# Connectors.net
KiCad netlist of a schematic drawn in Altium Designer
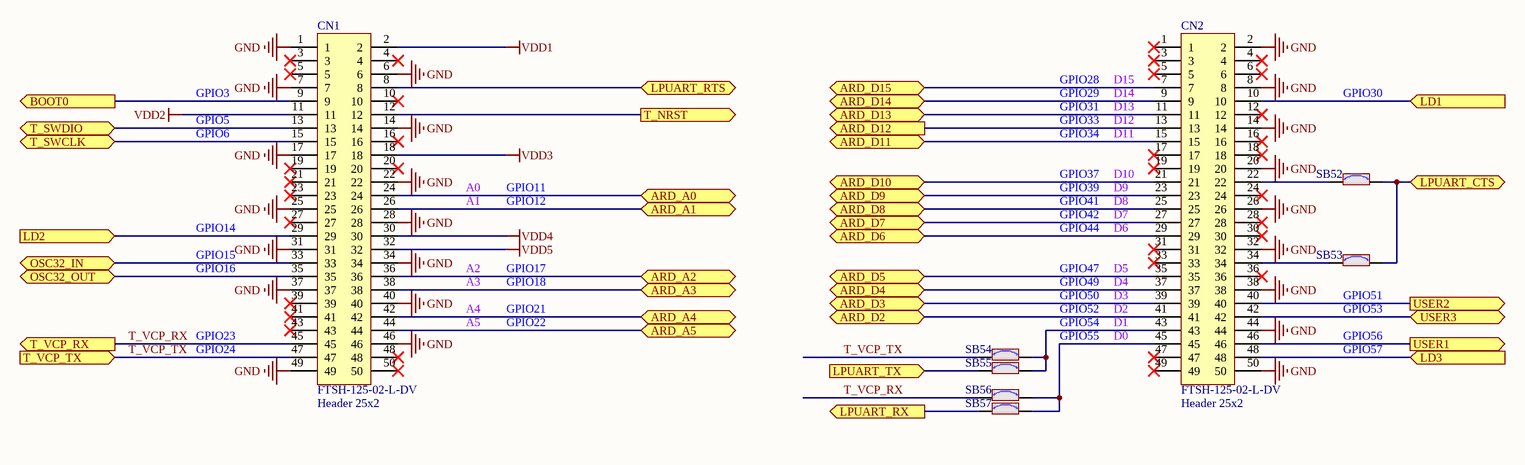
[diagram p0: Connectors.SchDoc]

(export (version "E")
  (design (tool "Eeschema 10.0.6"))
  (components
    (comp (ref "CN1")
      (value "FTSH-125-02-L-DV")
      (footprint "MCD_PARTS:CON_SAMTEC_FTSH-125-02-L-DV")
      (description "Header, 25x2, 12.7mm, VR, SMD, T=4.83mm")
      (fields
        (field (name "INTERNAL_PART_NUMBER") "MCD-02746")
        (field (name "ALTIUM_VALUE") "Header 25x2")
        (field (name "MANUFACTURER") "SAMTEC")
      )
      (libsource (lib "MCD_PARTS_database") (part "FTSH-125-02-L-DV"))
    )
    (comp (ref "CN2")
      (value "FTSH-125-02-L-DV")
      (footprint "MCD_PARTS:CON_SAMTEC_FTSH-125-02-L-DV")
      (description "Header, 25x2, 12.7mm, VR, SMD, T=4.83mm")
      (fields
        (field (name "INTERNAL_PART_NUMBER") "MCD-02746")
        (field (name "ALTIUM_VALUE") "Header 25x2")
        (field (name "MANUFACTURER") "SAMTEC")
      )
      (libsource (lib "MCD_PARTS_database") (part "FTSH-125-02-L-DV"))
    )
    (comp (ref "SB52")
      (value "SB_ON")
      (footprint "MCD_PARTS:SOLDER-BRIDGE_R0402-0R")
      (description "Solder Bridge 0402 ON")
      (fields (field (name "INTERNAL_PART_NUMBER") "MCD-01618") (field (name "MANUFACTURER") "YAGEO"))
      (libsource (lib "MCD_PARTS_database") (part "SB_ON"))
    )
    (comp (ref "SB53")
      (value "SB_ON")
      (footprint "MCD_PARTS:SOLDER-BRIDGE_R0402-0R")
      (description "Solder Bridge 0402 ON")
      (fields (field (name "INTERNAL_PART_NUMBER") "MCD-01618") (field (name "MANUFACTURER") "YAGEO"))
      (libsource (lib "MCD_PARTS_database") (part "SB_ON"))
    )
    (comp (ref "SB54")
      (value "SB_ON")
      (footprint "MCD_PARTS:SOLDER-BRIDGE_R0402-0R")
      (description "Solder Bridge 0402 ON")
      (fields (field (name "INTERNAL_PART_NUMBER") "MCD-01618") (field (name "MANUFACTURER") "YAGEO"))
      (libsource (lib "MCD_PARTS_database") (part "SB_ON"))
    )
    (comp (ref "SB55")
      (value "SB_ON")
      (footprint "MCD_PARTS:SOLDER-BRIDGE_R0402-0R")
      (description "Solder Bridge 0402 ON")
      (fields (field (name "INTERNAL_PART_NUMBER") "MCD-01618") (field (name "MANUFACTURER") "YAGEO"))
      (libsource (lib "MCD_PARTS_database") (part "SB_ON"))
    )
    (comp (ref "SB56")
      (value "SB_ON")
      (footprint "MCD_PARTS:SOLDER-BRIDGE_R0402-0R")
      (description "Solder Bridge 0402 ON")
      (fields (field (name "INTERNAL_PART_NUMBER") "MCD-01618") (field (name "MANUFACTURER") "YAGEO"))
      (libsource (lib "MCD_PARTS_database") (part "SB_ON"))
    )
    (comp (ref "SB57")
      (value "SB_ON")
      (footprint "MCD_PARTS:SOLDER-BRIDGE_R0402-0R")
      (description "Solder Bridge 0402 ON")
      (fields (field (name "INTERNAL_PART_NUMBER") "MCD-01618") (field (name "MANUFACTURER") "YAGEO"))
      (libsource (lib "MCD_PARTS_database") (part "SB_ON"))
    )
  )
  (nets
    (net (code "1") (name "/ARD_A0") (class "Default")
      (node (ref "CN1") (pin "24") (pinfunction "24_24") (pintype "passive"))
    )
    (net (code "2") (name "/ARD_A1") (class "Default")
      (node (ref "CN1") (pin "26") (pinfunction "26_26") (pintype "passive"))
    )
    (net (code "3") (name "/ARD_A2") (class "Default")
      (node (ref "CN1") (pin "36") (pinfunction "36_36") (pintype "passive"))
    )
    (net (code "4") (name "/ARD_A3") (class "Default")
      (node (ref "CN1") (pin "38") (pinfunction "38_38") (pintype "passive"))
    )
    (net (code "5") (name "/ARD_A4") (class "Default")
      (node (ref "CN1") (pin "42") (pinfunction "42_42") (pintype "passive"))
    )
    (net (code "6") (name "/ARD_A5") (class "Default")
      (node (ref "CN1") (pin "44") (pinfunction "44_44") (pintype "passive"))
    )
    (net (code "7") (name "/ARD_D2") (class "Default")
      (node (ref "CN2") (pin "41") (pinfunction "41_41") (pintype "passive"))
    )
    (net (code "8") (name "/ARD_D3") (class "Default")
      (node (ref "CN2") (pin "39") (pinfunction "39_39") (pintype "passive"))
    )
    (net (code "9") (name "/ARD_D4") (class "Default")
      (node (ref "CN2") (pin "37") (pinfunction "37_37") (pintype "passive"))
    )
    (net (code "10") (name "/ARD_D5") (class "Default")
      (node (ref "CN2") (pin "35") (pinfunction "35_35") (pintype "passive"))
    )
    (net (code "11") (name "/ARD_D6") (class "Default")
      (node (ref "CN2") (pin "29") (pinfunction "29_29") (pintype "passive"))
    )
    (net (code "12") (name "/ARD_D7") (class "Default")
      (node (ref "CN2") (pin "27") (pinfunction "27_27") (pintype "passive"))
    )
    (net (code "13") (name "/ARD_D8") (class "Default")
      (node (ref "CN2") (pin "25") (pinfunction "25_25") (pintype "passive"))
    )
    (net (code "14") (name "/ARD_D9") (class "Default")
      (node (ref "CN2") (pin "23") (pinfunction "23_23") (pintype "passive"))
    )
    (net (code "15") (name "/ARD_D10") (class "Default")
      (node (ref "CN2") (pin "21") (pinfunction "21_21") (pintype "passive"))
    )
    (net (code "16") (name "/ARD_D11") (class "Default")
      (node (ref "CN2") (pin "15") (pinfunction "15_15") (pintype "passive"))
    )
    (net (code "17") (name "/ARD_D12") (class "Default")
      (node (ref "CN2") (pin "13") (pinfunction "13_13") (pintype "passive"))
    )
    (net (code "18") (name "/ARD_D13") (class "Default")
      (node (ref "CN2") (pin "11") (pinfunction "11_11") (pintype "passive"))
    )
    (net (code "19") (name "/ARD_D14") (class "Default")
      (node (ref "CN2") (pin "9") (pinfunction "9_9") (pintype "passive"))
    )
    (net (code "20") (name "/ARD_D15") (class "Default")
      (node (ref "CN2") (pin "7") (pinfunction "7_7") (pintype "passive"))
    )
    (net (code "21") (name "/BOOT0") (class "Default")
      (node (ref "CN1") (pin "9") (pinfunction "9_9") (pintype "passive"))
    )
    (net (code "22") (name "/LD1") (class "Default")
      (node (ref "CN2") (pin "10") (pinfunction "10_10") (pintype "passive"))
    )
    (net (code "23") (name "/LD2") (class "Default")
      (node (ref "CN1") (pin "29") (pinfunction "29_29") (pintype "passive"))
    )
    (net (code "24") (name "/LD3") (class "Default")
      (node (ref "CN2") (pin "48") (pinfunction "48_48") (pintype "passive"))
    )
    (net (code "25") (name "/LPUART_CTS") (class "Default")
      (node (ref "SB52") (pin "2") (pinfunction "2_2") (pintype "passive"))
      (node (ref "SB53") (pin "2") (pinfunction "2_2") (pintype "passive"))
    )
    (net (code "26") (name "/LPUART_RTS") (class "Default")
      (node (ref "CN1") (pin "8") (pinfunction "8_8") (pintype "passive"))
    )
    (net (code "27") (name "/LPUART_RX") (class "Default")
      (node (ref "SB57") (pin "1") (pinfunction "1_1") (pintype "passive"))
    )
    (net (code "28") (name "/LPUART_TX") (class "Default")
      (node (ref "SB55") (pin "1") (pinfunction "1_1") (pintype "passive"))
    )
    (net (code "29") (name "/OSC32_IN") (class "Default")
      (node (ref "CN1") (pin "33") (pinfunction "33_33") (pintype "passive"))
    )
    (net (code "30") (name "/OSC32_OUT") (class "Default")
      (node (ref "CN1") (pin "35") (pinfunction "35_35") (pintype "passive"))
    )
    (net (code "31") (name "/T_NRST") (class "Default")
      (node (ref "CN1") (pin "12") (pinfunction "12_12") (pintype "passive"))
    )
    (net (code "32") (name "/T_SWCLK") (class "Default")
      (node (ref "CN1") (pin "15") (pinfunction "15_15") (pintype "passive"))
    )
    (net (code "33") (name "/T_SWDIO") (class "Default")
      (node (ref "CN1") (pin "13") (pinfunction "13_13") (pintype "passive"))
    )
    (net (code "34") (name "/T_VCP_RX") (class "Default")
      (node (ref "CN1") (pin "45") (pinfunction "45_45") (pintype "passive"))
      (node (ref "SB56") (pin "1") (pinfunction "1_1") (pintype "passive"))
    )
    (net (code "35") (name "/T_VCP_TX") (class "Default")
      (node (ref "CN1") (pin "47") (pinfunction "47_47") (pintype "passive"))
      (node (ref "SB54") (pin "1") (pinfunction "1_1") (pintype "passive"))
    )
    (net (code "36") (name "/USER1") (class "Default")
      (node (ref "CN2") (pin "46") (pinfunction "46_46") (pintype "passive"))
    )
    (net (code "37") (name "/USER2") (class "Default")
      (node (ref "CN2") (pin "40") (pinfunction "40_40") (pintype "passive"))
    )
    (net (code "38") (name "/USER3") (class "Default")
      (node (ref "CN2") (pin "42") (pinfunction "42_42") (pintype "passive"))
    )
    (net (code "39") (name "GND") (class "Default")
      (node (ref "CN1") (pin "1") (pinfunction "1_1") (pintype "passive"))
      (node (ref "CN1") (pin "14") (pinfunction "14_14") (pintype "passive"))
      (node (ref "CN1") (pin "17") (pinfunction "17_17") (pintype "passive"))
      (node (ref "CN1") (pin "22") (pinfunction "22_22") (pintype "passive"))
      (node (ref "CN1") (pin "25") (pinfunction "25_25") (pintype "passive"))
      (node (ref "CN1") (pin "28") (pinfunction "28_28") (pintype "passive"))
      (node (ref "CN1") (pin "31") (pinfunction "31_31") (pintype "passive"))
      (node (ref "CN1") (pin "34") (pinfunction "34_34") (pintype "passive"))
      (node (ref "CN1") (pin "37") (pinfunction "37_37") (pintype "passive"))
      (node (ref "CN1") (pin "40") (pinfunction "40_40") (pintype "passive"))
      (node (ref "CN1") (pin "46") (pinfunction "46_46") (pintype "passive"))
      (node (ref "CN1") (pin "49") (pinfunction "49_49") (pintype "passive"))
      (node (ref "CN1") (pin "6") (pinfunction "6_6") (pintype "passive"))
      (node (ref "CN1") (pin "7") (pinfunction "7_7") (pintype "passive"))
      (node (ref "CN2") (pin "14") (pinfunction "14_14") (pintype "passive"))
      (node (ref "CN2") (pin "2") (pinfunction "2_2") (pintype "passive"))
      (node (ref "CN2") (pin "20") (pinfunction "20_20") (pintype "passive"))
      (node (ref "CN2") (pin "26") (pinfunction "26_26") (pintype "passive"))
      (node (ref "CN2") (pin "32") (pinfunction "32_32") (pintype "passive"))
      (node (ref "CN2") (pin "38") (pinfunction "38_38") (pintype "passive"))
      (node (ref "CN2") (pin "44") (pinfunction "44_44") (pintype "passive"))
      (node (ref "CN2") (pin "50") (pinfunction "50_50") (pintype "passive"))
      (node (ref "CN2") (pin "8") (pinfunction "8_8") (pintype "passive"))
    )
    (net (code "40") (name "Net-(CN2-Pad22)") (class "Default")
      (node (ref "CN2") (pin "22") (pinfunction "22_22") (pintype "passive"))
      (node (ref "SB52") (pin "1") (pinfunction "1_1") (pintype "passive"))
    )
    (net (code "41") (name "Net-(CN2-Pad34)") (class "Default")
      (node (ref "CN2") (pin "34") (pinfunction "34_34") (pintype "passive"))
      (node (ref "SB53") (pin "1") (pinfunction "1_1") (pintype "passive"))
    )
    (net (code "42") (name "Net-(CN2-Pad43)") (class "Default")
      (node (ref "CN2") (pin "43") (pinfunction "43_43") (pintype "passive"))
      (node (ref "SB54") (pin "2") (pinfunction "2_2") (pintype "passive"))
      (node (ref "SB55") (pin "2") (pinfunction "2_2") (pintype "passive"))
    )
    (net (code "43") (name "Net-(CN2-Pad45)") (class "Default")
      (node (ref "CN2") (pin "45") (pinfunction "45_45") (pintype "passive"))
      (node (ref "SB56") (pin "2") (pinfunction "2_2") (pintype "passive"))
      (node (ref "SB57") (pin "2") (pinfunction "2_2") (pintype "passive"))
    )
    (net (code "44") (name "VDD1") (class "Default")
      (node (ref "CN1") (pin "2") (pinfunction "2_2") (pintype "passive"))
    )
    (net (code "45") (name "VDD2") (class "Default")
      (node (ref "CN1") (pin "11") (pinfunction "11_11") (pintype "passive"))
    )
    (net (code "46") (name "VDD3") (class "Default")
      (node (ref "CN1") (pin "18") (pinfunction "18_18") (pintype "passive"))
    )
    (net (code "47") (name "VDD4") (class "Default")
      (node (ref "CN1") (pin "30") (pinfunction "30_30") (pintype "passive"))
    )
    (net (code "48") (name "VDD5") (class "Default")
      (node (ref "CN1") (pin "32") (pinfunction "32_32") (pintype "passive"))
    )
    (net (code "49") (name "unconnected-(CN1-Pad3)") (class "Default")
      (node (ref "CN1") (pin "3") (pinfunction "3_3") (pintype "passive+no_connect"))
    )
    (net (code "50") (name "unconnected-(CN1-Pad4)") (class "Default")
      (node (ref "CN1") (pin "4") (pinfunction "4_4") (pintype "passive+no_connect"))
    )
    (net (code "51") (name "unconnected-(CN1-Pad5)") (class "Default")
      (node (ref "CN1") (pin "5") (pinfunction "5_5") (pintype "passive+no_connect"))
    )
    (net (code "52") (name "unconnected-(CN1-Pad10)") (class "Default")
      (node (ref "CN1") (pin "10") (pinfunction "10_10") (pintype "passive+no_connect"))
    )
    (net (code "53") (name "unconnected-(CN1-Pad16)") (class "Default")
      (node (ref "CN1") (pin "16") (pinfunction "16_16") (pintype "passive+no_connect"))
    )
    (net (code "54") (name "unconnected-(CN1-Pad19)") (class "Default")
      (node (ref "CN1") (pin "19") (pinfunction "19_19") (pintype "passive+no_connect"))
    )
    (net (code "55") (name "unconnected-(CN1-Pad20)") (class "Default")
      (node (ref "CN1") (pin "20") (pinfunction "20_20") (pintype "passive+no_connect"))
    )
    (net (code "56") (name "unconnected-(CN1-Pad21)") (class "Default")
      (node (ref "CN1") (pin "21") (pinfunction "21_21") (pintype "passive+no_connect"))
    )
    (net (code "57") (name "unconnected-(CN1-Pad23)") (class "Default")
      (node (ref "CN1") (pin "23") (pinfunction "23_23") (pintype "passive+no_connect"))
    )
    (net (code "58") (name "unconnected-(CN1-Pad27)") (class "Default")
      (node (ref "CN1") (pin "27") (pinfunction "27_27") (pintype "passive+no_connect"))
    )
    (net (code "59") (name "unconnected-(CN1-Pad39)") (class "Default")
      (node (ref "CN1") (pin "39") (pinfunction "39_39") (pintype "passive+no_connect"))
    )
    (net (code "60") (name "unconnected-(CN1-Pad41)") (class "Default")
      (node (ref "CN1") (pin "41") (pinfunction "41_41") (pintype "passive+no_connect"))
    )
    (net (code "61") (name "unconnected-(CN1-Pad43)") (class "Default")
      (node (ref "CN1") (pin "43") (pinfunction "43_43") (pintype "passive+no_connect"))
    )
    (net (code "62") (name "unconnected-(CN1-Pad48)") (class "Default")
      (node (ref "CN1") (pin "48") (pinfunction "48_48") (pintype "passive+no_connect"))
    )
    (net (code "63") (name "unconnected-(CN1-Pad50)") (class "Default")
      (node (ref "CN1") (pin "50") (pinfunction "50_50") (pintype "passive+no_connect"))
    )
    (net (code "64") (name "unconnected-(CN2-Pad1)") (class "Default")
      (node (ref "CN2") (pin "1") (pinfunction "1_1") (pintype "passive+no_connect"))
    )
    (net (code "65") (name "unconnected-(CN2-Pad3)") (class "Default")
      (node (ref "CN2") (pin "3") (pinfunction "3_3") (pintype "passive+no_connect"))
    )
    (net (code "66") (name "unconnected-(CN2-Pad4)") (class "Default")
      (node (ref "CN2") (pin "4") (pinfunction "4_4") (pintype "passive+no_connect"))
    )
    (net (code "67") (name "unconnected-(CN2-Pad5)") (class "Default")
      (node (ref "CN2") (pin "5") (pinfunction "5_5") (pintype "passive+no_connect"))
    )
    (net (code "68") (name "unconnected-(CN2-Pad6)") (class "Default")
      (node (ref "CN2") (pin "6") (pinfunction "6_6") (pintype "passive+no_connect"))
    )
    (net (code "69") (name "unconnected-(CN2-Pad12)") (class "Default")
      (node (ref "CN2") (pin "12") (pinfunction "12_12") (pintype "passive+no_connect"))
    )
    (net (code "70") (name "unconnected-(CN2-Pad16)") (class "Default")
      (node (ref "CN2") (pin "16") (pinfunction "16_16") (pintype "passive+no_connect"))
    )
    (net (code "71") (name "unconnected-(CN2-Pad17)") (class "Default")
      (node (ref "CN2") (pin "17") (pinfunction "17_17") (pintype "passive+no_connect"))
    )
    (net (code "72") (name "unconnected-(CN2-Pad18)") (class "Default")
      (node (ref "CN2") (pin "18") (pinfunction "18_18") (pintype "passive+no_connect"))
    )
    (net (code "73") (name "unconnected-(CN2-Pad19)") (class "Default")
      (node (ref "CN2") (pin "19") (pinfunction "19_19") (pintype "passive+no_connect"))
    )
    (net (code "74") (name "unconnected-(CN2-Pad24)") (class "Default")
      (node (ref "CN2") (pin "24") (pinfunction "24_24") (pintype "passive+no_connect"))
    )
    (net (code "75") (name "unconnected-(CN2-Pad28)") (class "Default")
      (node (ref "CN2") (pin "28") (pinfunction "28_28") (pintype "passive+no_connect"))
    )
    (net (code "76") (name "unconnected-(CN2-Pad30)") (class "Default")
      (node (ref "CN2") (pin "30") (pinfunction "30_30") (pintype "passive+no_connect"))
    )
    (net (code "77") (name "unconnected-(CN2-Pad31)") (class "Default")
      (node (ref "CN2") (pin "31") (pinfunction "31_31") (pintype "passive+no_connect"))
    )
    (net (code "78") (name "unconnected-(CN2-Pad33)") (class "Default")
      (node (ref "CN2") (pin "33") (pinfunction "33_33") (pintype "passive+no_connect"))
    )
    (net (code "79") (name "unconnected-(CN2-Pad36)") (class "Default")
      (node (ref "CN2") (pin "36") (pinfunction "36_36") (pintype "passive+no_connect"))
    )
    (net (code "80") (name "unconnected-(CN2-Pad47)") (class "Default")
      (node (ref "CN2") (pin "47") (pinfunction "47_47") (pintype "passive+no_connect"))
    )
    (net (code "81") (name "unconnected-(CN2-Pad49)") (class "Default")
      (node (ref "CN2") (pin "49") (pinfunction "49_49") (pintype "passive+no_connect"))
    )
  )
)
